# MasterShematic.net
KiCad netlist of a schematic drawn in Altium Designer
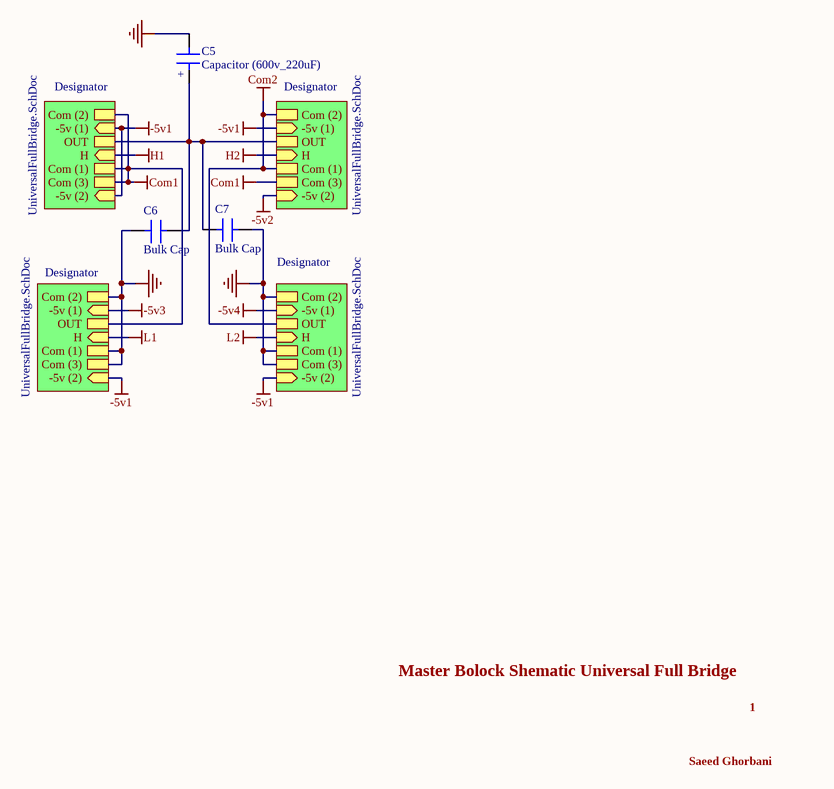
[diagram p0: MasterShematic.SchDoc]

(export (version "E")
  (design (tool "Eeschema 10.0.6"))
  (components
    (comp (ref "C5")
      (value "Capacitor (600v_220uF)")
      (libsource (lib "UniversalFullBridge") (part "Capacitor (600v_220uF)"))
    )
    (comp (ref "C6")
      (value "Bulk Cap")
      (libsource (lib "UniversalFullBridge") (part "Capcitor (3300pF Bulk)"))
    )
    (comp (ref "C7")
      (value "Bulk Cap")
      (libsource (lib "UniversalFullBridge") (part "Capcitor (3300pF Bulk)"))
    )
  )
  (nets
    (net (code "5") (name "/OUT") (class "Default")
      (node (ref "C5") (pin "1") (pinfunction "1_1") (pintype "passive"))
      (node (ref "C6") (pin "1") (pinfunction "1_1") (pintype "passive"))
      (node (ref "C7") (pin "2") (pinfunction "2_2") (pintype "passive"))
    )
    (net (code "8") (name "GND") (class "Default")
      (node (ref "C5") (pin "2") (pinfunction "2_2") (pintype "passive"))
      (node (ref "C6") (pin "2") (pinfunction "2_2") (pintype "passive"))
      (node (ref "C7") (pin "1") (pinfunction "1_1") (pintype "passive"))
    )
  )
)
